# T_Phase_Sense_Signal_Isolation.net
KiCad netlist of a schematic drawn in Altium Designer
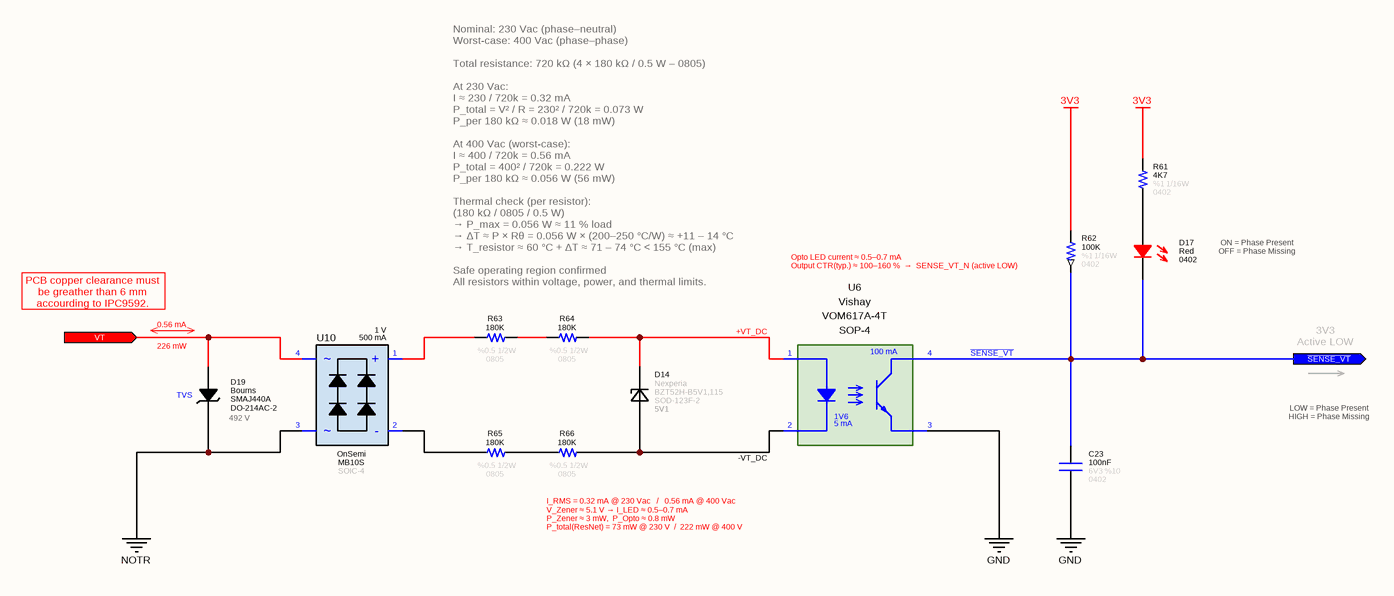
[diagram p0: T Phase Sense Signal Isolation.SchDoc]

(export (version "E")
  (design (tool "Eeschema 10.0.6"))
  (components
    (comp (ref "C23")
      (value "100nF")
      (footprint "CAPACITOR_0402")
      (description "Capacitor (MLCC) - 100nF / 6V3 / 0402")
      (fields
        (field (name "MANUFACTURER PART NUMBER") "04026D104KAT4A")
        (field (name "TOLERANCE") "%10")
        (field (name "VOLTAGE") "6V3")
        (field (name "CASE") "0402")
        (field (name "Comment") "Capacitor - 100nF [0402] (MLCC)")
      )
      (libsource (lib "Akkoyun") (part "Capacitor - 100nF [0402-6V3]"))
    )
    (comp (ref "D14")
      (value "BZT52H-B5V1,115")
      (footprint "SOD-123F-2")
      (description "Zener Diodes BZT52H-B5V1/SOD123F/SOD2")
      (fields
        (field (name "ZENER VOLTAGE") "5V1")
        (field (name "MANUFACTURER NAME") "Nexperia")
        (field (name "MANUFACTURER PART NUMBER") "BZT52H-B5V1,115")
        (field (name "CASE") "SOD-123F-2")
      )
      (libsource (lib "Akkoyun") (part "Diode - BZT52H-B5V1,115"))
    )
    (comp (ref "D17")
      (value "SMD LED (Red)")
      (footprint "LED_0402")
      (description "Standard LEDs - SMD MINI-MOLD ULTRA COMPACT RED")
      (fields
        (field (name "MANUFACTURER PART NUMBER") "SML-P12VTT86R")
        (field (name "CASE") "0402")
        (field (name "COLOR") "Red")
      )
      (libsource (lib "Akkoyun") (part "Diode - LED (0402-Red)"))
    )
    (comp (ref "D19")
      (value "SMAJ440A")
      (footprint "DO-220AA-2")
      (description "ESD Protection Diodes / TVS Diodes 440volts 1uA .6 Amps Uni-Dir")
      (fields
        (field (name "BREAKDOWN VOLTAGE") "492 V")
        (field (name "MANUFACTURER NAME") "Bourns")
        (field (name "MANUFACTURER PART NUMBER") "SMAJ440A")
        (field (name "CASE") "DO-214AC-2")
      )
      (libsource (lib "Akkoyun") (part "Diode - SMAJ440A (TVS)"))
    )
    (comp (ref "R61")
      (value "4K7")
      (footprint "RESISTOR_0402")
      (description "Thick Film Resistors - SMD 1/16 W 4.7 KOhm 1%")
      (fields
        (field (name "MANUFACTURER PART NUMBER") "CRCW04024K70FKED")
        (field (name "TOLERANCE") "%1")
        (field (name "CASE") "0402")
        (field (name "POWER") "1/16W")
        (field (name "Comment") "4K7 - 0402 - %1 - 1/16W")
      )
      (libsource (lib "Akkoyun") (part "Resistor - 4K7 [0402]"))
    )
    (comp (ref "R62")
      (value "100K")
      (footprint "RESISTOR_0402")
      (description "Thick Film Resistors - SMD 1/16 W 100 KOhm 1%")
      (fields
        (field (name "MANUFACTURER PART NUMBER") "CRCW0402100KFKED")
        (field (name "TOLERANCE") "%1")
        (field (name "CASE") "0402")
        (field (name "POWER") "1/16W")
        (field (name "Comment") "100K - 0402 - %1 - 1/16W")
      )
      (libsource (lib "Akkoyun") (part "Resistor - 100K [0402]"))
    )
    (comp (ref "R63")
      (value "180K")
      (footprint "RESISTOR_0805")
      (description "Thick Film Resistors - SMD 0805 180Kohms 0.5W 0.5% AEC-Q200")
      (fields
        (field (name "MANUFACTURER PART NUMBER") "ERJ-P06D1803V")
        (field (name "TOLERANCE") "%0.5")
        (field (name "CASE") "0805")
        (field (name "POWER") "1/2W")
        (field (name "Comment") "180K - 0805 - %0.5 - 1/2W")
      )
      (libsource (lib "Akkoyun") (part "Resistor - 180K [0805]"))
    )
    (comp (ref "R64")
      (value "180K")
      (footprint "RESISTOR_0805")
      (description "Thick Film Resistors - SMD 0805 180Kohms 0.5W 0.5% AEC-Q200")
      (fields
        (field (name "MANUFACTURER PART NUMBER") "ERJ-P06D1803V")
        (field (name "TOLERANCE") "%0.5")
        (field (name "CASE") "0805")
        (field (name "POWER") "1/2W")
        (field (name "Comment") "180K - 0805 - %0.5 - 1/2W")
      )
      (libsource (lib "Akkoyun") (part "Resistor - 180K [0805]"))
    )
    (comp (ref "R65")
      (value "180K")
      (footprint "RESISTOR_0805")
      (description "Thick Film Resistors - SMD 0805 180Kohms 0.5W 0.5% AEC-Q200")
      (fields
        (field (name "MANUFACTURER PART NUMBER") "ERJ-P06D1803V")
        (field (name "TOLERANCE") "%0.5")
        (field (name "CASE") "0805")
        (field (name "POWER") "1/2W")
        (field (name "Comment") "180K - 0805 - %0.5 - 1/2W")
      )
      (libsource (lib "Akkoyun") (part "Resistor - 180K [0805]"))
    )
    (comp (ref "R66")
      (value "180K")
      (footprint "RESISTOR_0805")
      (description "Thick Film Resistors - SMD 0805 180Kohms 0.5W 0.5% AEC-Q200")
      (fields
        (field (name "MANUFACTURER PART NUMBER") "ERJ-P06D1803V")
        (field (name "TOLERANCE") "%0.5")
        (field (name "CASE") "0805")
        (field (name "POWER") "1/2W")
        (field (name "Comment") "180K - 0805 - %0.5 - 1/2W")
      )
      (libsource (lib "Akkoyun") (part "Resistor - 180K [0805]"))
    )
    (comp (ref "U6")
      (value "VOM617A-4T")
      (footprint "SOP-4V2")
      (description "Transistor Output Optocouplers Phototransistor Out CTR 160-320% 5mA")
      (fields
        (field (name "MANUFACTURER PART NUMBER") "VOM617A-4T")
        (field (name "MANUFACTURER NAME") "Vishay")
        (field (name "CASE") "SOP-4")
        (field (name "IF - FORWARD CURRENT") "5 mA")
        (field (name "VF - FORWARD VOLTAGE") "1V6")
        (field (name "MAXIMUM COLLECTOR CURRENT") "100 mA")
      )
      (libsource (lib "Akkoyun") (part "IC - VOM617A"))
    )
    (comp (ref "U10")
      (value "LTV-846S")
      (footprint "SOIC-4")
      (description "Transistor Output Optocouplers Optocplr Phototrans 4-Channel")
      (fields
        (field (name "IF - FORWARD CURRENT") "500 mA")
        (field (name "VF - FORWARD VOLTAGE") "1 V")
        (field (name "MANUFACTURER NAME") "OnSemi")
        (field (name "MANUFACTURER PART NUMBER") "MB10S")
        (field (name "CASE") "SOIC-4")
      )
      (libsource (lib "Akkoyun") (part "IC - MB10S"))
    )
  )
  (nets
    (net (code "1") (name "/+VT_DC") (class "Default")
      (node (ref "D14") (pin "1") (pinfunction "Cathode_1") (pintype "passive"))
      (node (ref "R64") (pin "1") (pinfunction "1_1") (pintype "passive"))
      (node (ref "U6") (pin "1") (pinfunction "LED_Anode_1") (pintype "passive"))
    )
    (net (code "2") (name "/-VT_DC") (class "Default")
      (node (ref "D14") (pin "2") (pinfunction "Anode_2") (pintype "passive"))
      (node (ref "R66") (pin "1") (pinfunction "1_1") (pintype "passive"))
      (node (ref "U6") (pin "2") (pinfunction "LED_Cathode_2") (pintype "passive"))
    )
    (net (code "3") (name "/VT") (class "Default")
      (node (ref "D19") (pin "1") (pinfunction "Anode_1") (pintype "passive"))
      (node (ref "U10") (pin "4") (pinfunction "~_4") (pintype "passive"))
    )
    (net (code "4") (name "/~{SENSE_VT}") (class "Default")
      (node (ref "C23") (pin "2") (pinfunction "2_2") (pintype "passive"))
      (node (ref "D17") (pin "1") (pinfunction "1_1") (pintype "passive"))
      (node (ref "R62") (pin "1") (pinfunction "1_1") (pintype "output"))
      (node (ref "U6") (pin "4") (pinfunction "Collector_4") (pintype "passive"))
    )
    (net (code "5") (name "3V3") (class "Default")
      (node (ref "R61") (pin "2") (pinfunction "2_2") (pintype "passive"))
      (node (ref "R62") (pin "2") (pinfunction "2_2") (pintype "passive"))
    )
    (net (code "6") (name "GND") (class "Default")
      (node (ref "C23") (pin "1") (pinfunction "1_1") (pintype "passive"))
      (node (ref "U6") (pin "3") (pinfunction "Emiter_3") (pintype "passive"))
    )
    (net (code "7") (name "NOTR") (class "Default")
      (node (ref "D19") (pin "2") (pinfunction "Cathode_2") (pintype "passive"))
      (node (ref "U10") (pin "3") (pinfunction "~_3") (pintype "passive"))
    )
    (net (code "8") (name "Net-(D17-Pad2)") (class "Default")
      (node (ref "D17") (pin "2") (pinfunction "2_2") (pintype "passive"))
      (node (ref "R61") (pin "1") (pinfunction "1_1") (pintype "passive"))
    )
    (net (code "9") (name "Net-(R63-Pad1)") (class "Default")
      (node (ref "R63") (pin "1") (pinfunction "1_1") (pintype "passive"))
      (node (ref "R64") (pin "2") (pinfunction "2_2") (pintype "passive"))
    )
    (net (code "10") (name "Net-(R65-Pad1)") (class "Default")
      (node (ref "R65") (pin "1") (pinfunction "1_1") (pintype "passive"))
      (node (ref "R66") (pin "2") (pinfunction "2_2") (pintype "passive"))
    )
    (net (code "11") (name "Net-(U10-+)") (class "Default")
      (node (ref "R63") (pin "2") (pinfunction "2_2") (pintype "passive"))
      (node (ref "U10") (pin "1") (pinfunction "+_1") (pintype "passive"))
    )
    (net (code "12") (name "Net-(U10--)") (class "Default")
      (node (ref "R65") (pin "2") (pinfunction "2_2") (pintype "passive"))
      (node (ref "U10") (pin "2") (pinfunction "-_2") (pintype "passive"))
    )
  )
)
